# 104-de-8.net
KiCad netlist of a schematic drawn in EAGLE
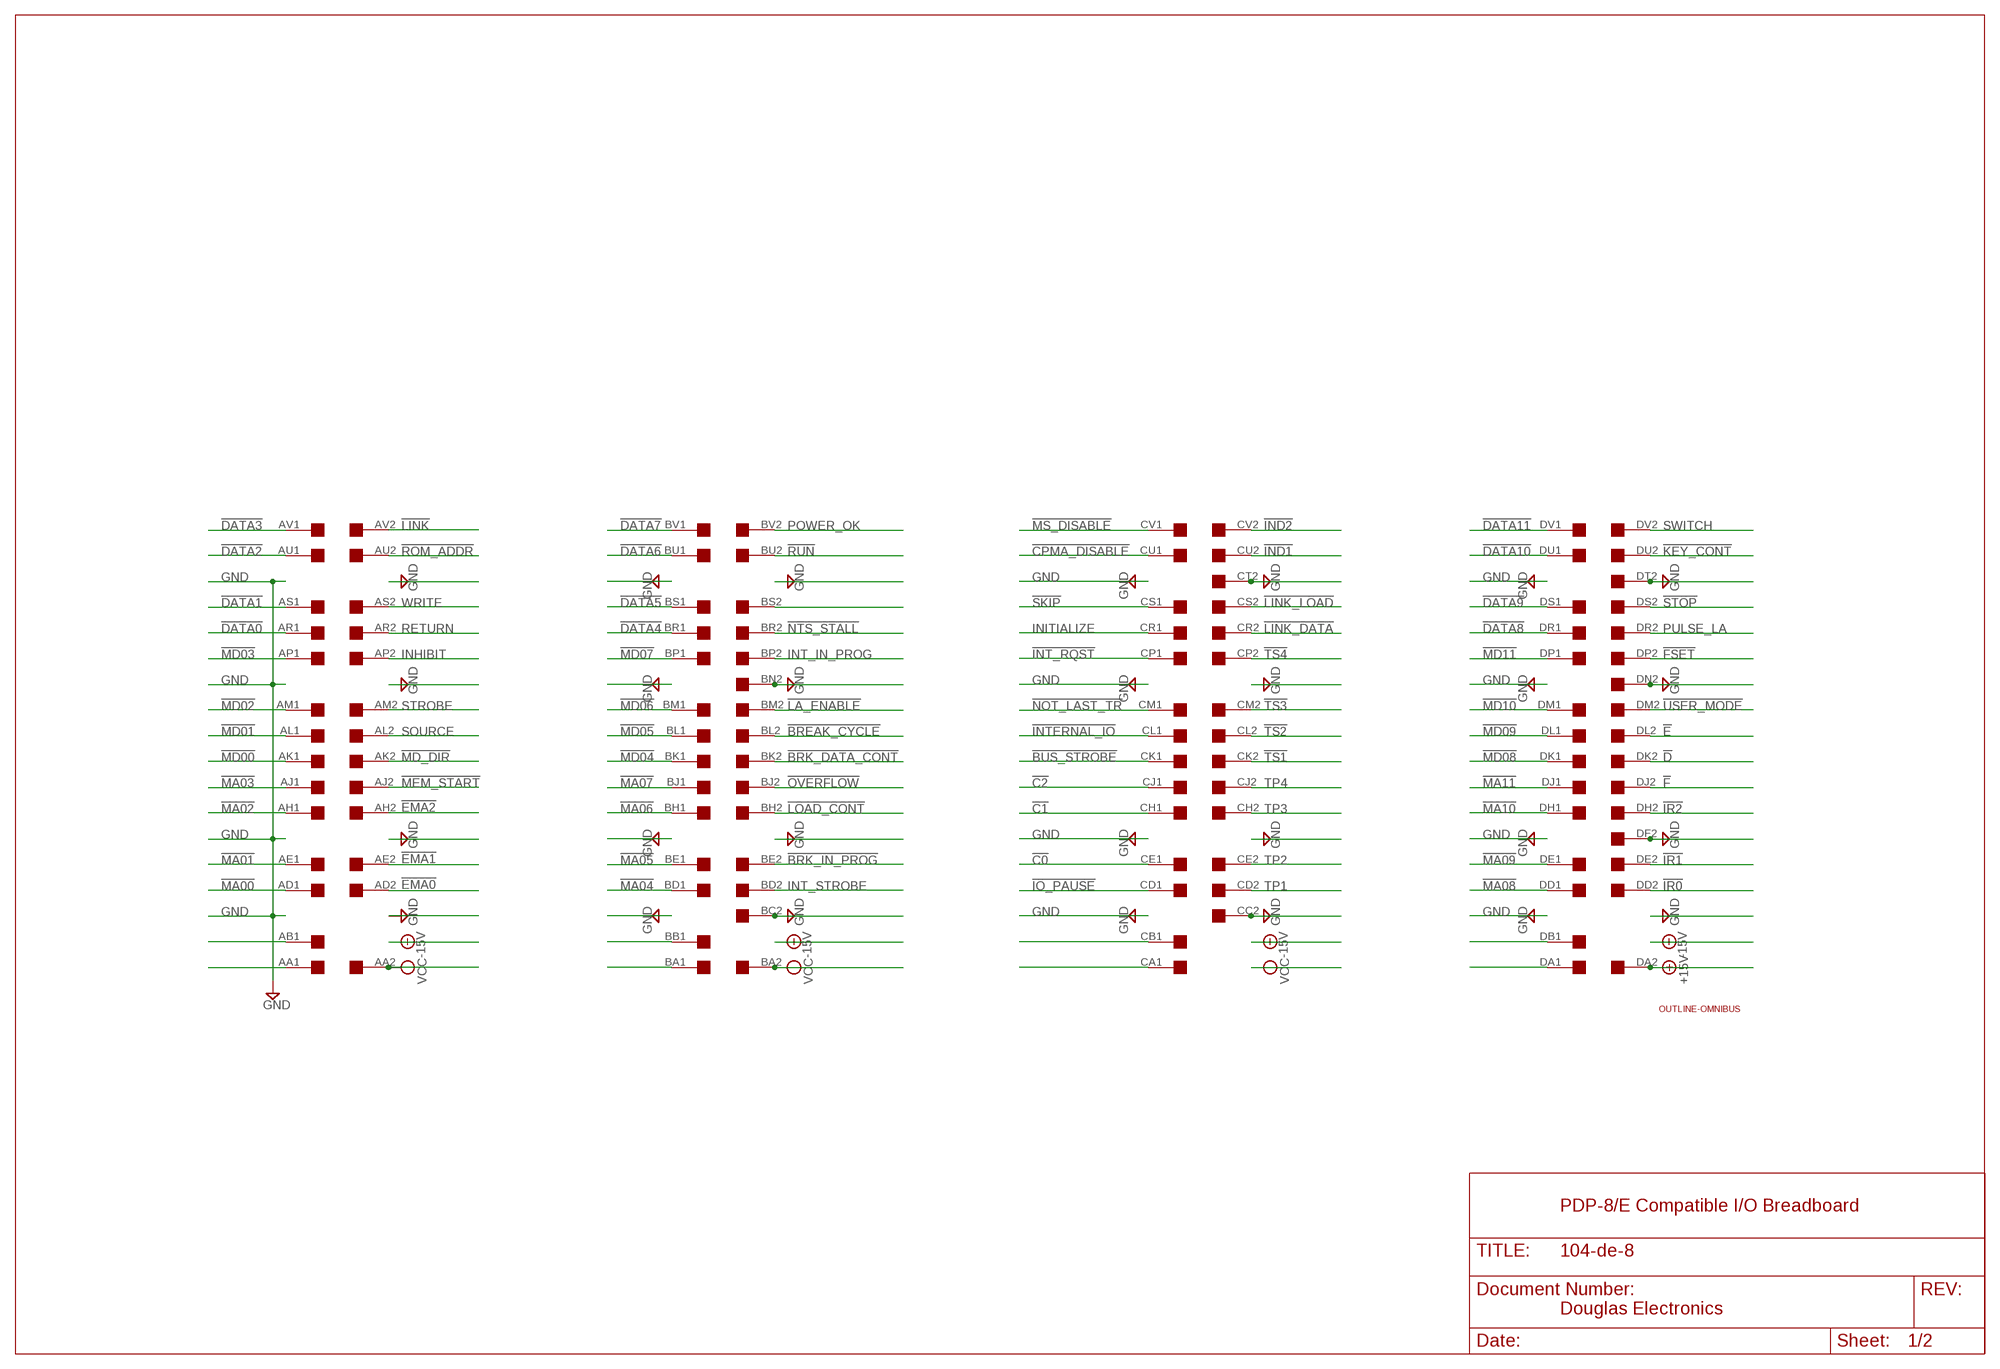
[diagram p0: schematic, sheet 1]
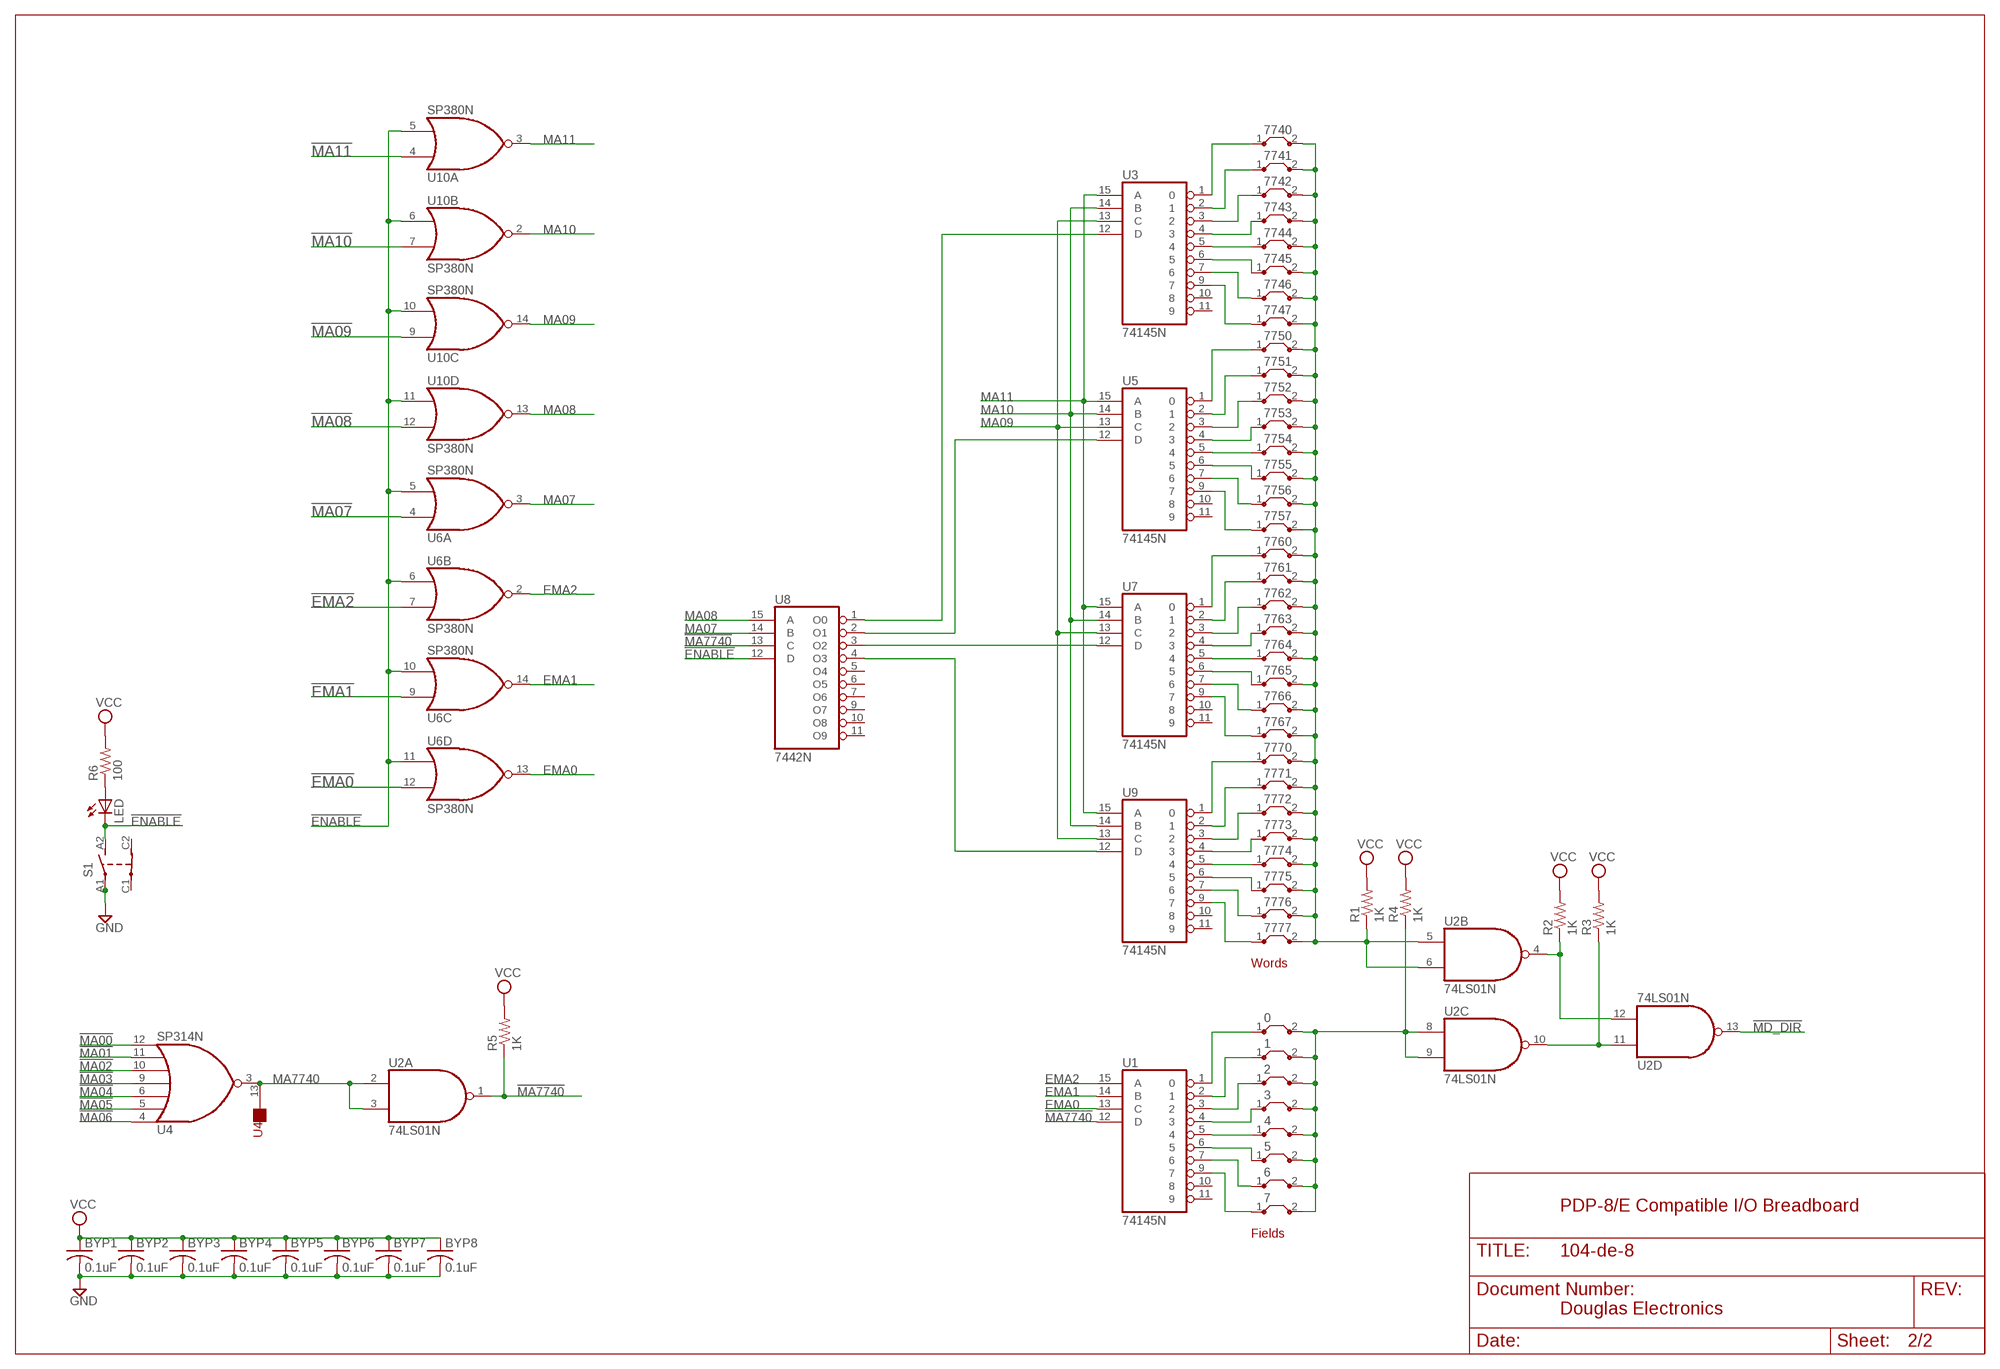
[diagram p1: schematic, sheet 2]

(export (version "E")
  (design (tool "Eeschema 10.0.6"))
  (components
    (comp (ref "0")
      (value "J5MM")
      (footprint "eagle-import:05")
      (libsource (lib "eagle-import") (part "J5MM"))
    )
    (comp (ref "1")
      (value "J5MM")
      (footprint "eagle-import:05")
      (libsource (lib "eagle-import") (part "J5MM"))
    )
    (comp (ref "2")
      (value "J5MM")
      (footprint "eagle-import:05")
      (libsource (lib "eagle-import") (part "J5MM"))
    )
    (comp (ref "3")
      (value "J5MM")
      (footprint "eagle-import:05")
      (libsource (lib "eagle-import") (part "J5MM"))
    )
    (comp (ref "4")
      (value "J5MM")
      (footprint "eagle-import:05")
      (libsource (lib "eagle-import") (part "J5MM"))
    )
    (comp (ref "5")
      (value "J5MM")
      (footprint "eagle-import:05")
      (libsource (lib "eagle-import") (part "J5MM"))
    )
    (comp (ref "6")
      (value "J5MM")
      (footprint "eagle-import:05")
      (libsource (lib "eagle-import") (part "J5MM"))
    )
    (comp (ref "7")
      (value "J5MM")
      (footprint "eagle-import:05")
      (libsource (lib "eagle-import") (part "J5MM"))
    )
    (comp (ref "7740")
      (value "J5MM")
      (footprint "eagle-import:05")
      (libsource (lib "eagle-import") (part "J5MM"))
    )
    (comp (ref "7741")
      (value "J5MM")
      (footprint "eagle-import:05")
      (libsource (lib "eagle-import") (part "J5MM"))
    )
    (comp (ref "7742")
      (value "J5MM")
      (footprint "eagle-import:05")
      (libsource (lib "eagle-import") (part "J5MM"))
    )
    (comp (ref "7743")
      (value "J5MM")
      (footprint "eagle-import:05")
      (libsource (lib "eagle-import") (part "J5MM"))
    )
    (comp (ref "7744")
      (value "J5MM")
      (footprint "eagle-import:05")
      (libsource (lib "eagle-import") (part "J5MM"))
    )
    (comp (ref "7745")
      (value "J5MM")
      (footprint "eagle-import:05")
      (libsource (lib "eagle-import") (part "J5MM"))
    )
    (comp (ref "7746")
      (value "J5MM")
      (footprint "eagle-import:05")
      (libsource (lib "eagle-import") (part "J5MM"))
    )
    (comp (ref "7747")
      (value "J5MM")
      (footprint "eagle-import:05")
      (libsource (lib "eagle-import") (part "J5MM"))
    )
    (comp (ref "7750")
      (value "J5MM")
      (footprint "eagle-import:05")
      (libsource (lib "eagle-import") (part "J5MM"))
    )
    (comp (ref "7751")
      (value "J5MM")
      (footprint "eagle-import:05")
      (libsource (lib "eagle-import") (part "J5MM"))
    )
    (comp (ref "7752")
      (value "J5MM")
      (footprint "eagle-import:05")
      (libsource (lib "eagle-import") (part "J5MM"))
    )
    (comp (ref "7753")
      (value "J5MM")
      (footprint "eagle-import:05")
      (libsource (lib "eagle-import") (part "J5MM"))
    )
    (comp (ref "7754")
      (value "J5MM")
      (footprint "eagle-import:05")
      (libsource (lib "eagle-import") (part "J5MM"))
    )
    (comp (ref "7755")
      (value "J5MM")
      (footprint "eagle-import:05")
      (libsource (lib "eagle-import") (part "J5MM"))
    )
    (comp (ref "7756")
      (value "J5MM")
      (footprint "eagle-import:05")
      (libsource (lib "eagle-import") (part "J5MM"))
    )
    (comp (ref "7757")
      (value "J5MM")
      (footprint "eagle-import:05")
      (libsource (lib "eagle-import") (part "J5MM"))
    )
    (comp (ref "7760")
      (value "J5MM")
      (footprint "eagle-import:05")
      (libsource (lib "eagle-import") (part "J5MM"))
    )
    (comp (ref "7761")
      (value "J5MM")
      (footprint "eagle-import:05")
      (libsource (lib "eagle-import") (part "J5MM"))
    )
    (comp (ref "7762")
      (value "J5MM")
      (footprint "eagle-import:05")
      (libsource (lib "eagle-import") (part "J5MM"))
    )
    (comp (ref "7763")
      (value "J5MM")
      (footprint "eagle-import:05")
      (libsource (lib "eagle-import") (part "J5MM"))
    )
    (comp (ref "7764")
      (value "J5MM")
      (footprint "eagle-import:05")
      (libsource (lib "eagle-import") (part "J5MM"))
    )
    (comp (ref "7765")
      (value "J5MM")
      (footprint "eagle-import:05")
      (libsource (lib "eagle-import") (part "J5MM"))
    )
    (comp (ref "7766")
      (value "J5MM")
      (footprint "eagle-import:05")
      (libsource (lib "eagle-import") (part "J5MM"))
    )
    (comp (ref "7767")
      (value "J5MM")
      (footprint "eagle-import:05")
      (libsource (lib "eagle-import") (part "J5MM"))
    )
    (comp (ref "7770")
      (value "J5MM")
      (footprint "eagle-import:05")
      (libsource (lib "eagle-import") (part "J5MM"))
    )
    (comp (ref "7771")
      (value "J5MM")
      (footprint "eagle-import:05")
      (libsource (lib "eagle-import") (part "J5MM"))
    )
    (comp (ref "7772")
      (value "J5MM")
      (footprint "eagle-import:05")
      (libsource (lib "eagle-import") (part "J5MM"))
    )
    (comp (ref "7773")
      (value "J5MM")
      (footprint "eagle-import:05")
      (libsource (lib "eagle-import") (part "J5MM"))
    )
    (comp (ref "7774")
      (value "J5MM")
      (footprint "eagle-import:05")
      (libsource (lib "eagle-import") (part "J5MM"))
    )
    (comp (ref "7775")
      (value "J5MM")
      (footprint "eagle-import:05")
      (libsource (lib "eagle-import") (part "J5MM"))
    )
    (comp (ref "7776")
      (value "J5MM")
      (footprint "eagle-import:05")
      (libsource (lib "eagle-import") (part "J5MM"))
    )
    (comp (ref "7777")
      (value "J5MM")
      (footprint "eagle-import:05")
      (libsource (lib "eagle-import") (part "J5MM"))
    )
    (comp (ref "BYP1")
      (value "0.1uF")
      (footprint "eagle-import:C063-025X075")
      (libsource (lib "eagle-import") (part "C-US"))
    )
    (comp (ref "BYP2")
      (value "0.1uF")
      (footprint "eagle-import:C063-025X075")
      (libsource (lib "eagle-import") (part "C-US"))
    )
    (comp (ref "BYP3")
      (value "0.1uF")
      (footprint "eagle-import:C063-025X075")
      (libsource (lib "eagle-import") (part "C-US"))
    )
    (comp (ref "BYP4")
      (value "0.1uF")
      (footprint "eagle-import:C063-025X075")
      (libsource (lib "eagle-import") (part "C-US"))
    )
    (comp (ref "BYP5")
      (value "0.1uF")
      (footprint "eagle-import:C063-025X075")
      (libsource (lib "eagle-import") (part "C-US"))
    )
    (comp (ref "BYP6")
      (value "0.1uF")
      (footprint "eagle-import:C063-025X075")
      (libsource (lib "eagle-import") (part "C-US"))
    )
    (comp (ref "BYP7")
      (value "0.1uF")
      (footprint "eagle-import:C063-025X075")
      (libsource (lib "eagle-import") (part "C-US"))
    )
    (comp (ref "BYP8")
      (value "0.1uF")
      (footprint "eagle-import:C063-025X075")
      (libsource (lib "eagle-import") (part "C-US"))
    )
    (comp (ref "LED")
      (value "LED5MM")
      (footprint "eagle-import:LED5MM")
      (libsource (lib "eagle-import") (part "LED5MM"))
    )
    (comp (ref "R1")
      (value "1K")
      (footprint "eagle-import:0207_10")
      (libsource (lib "eagle-import") (part "R-US_0207/10"))
    )
    (comp (ref "R2")
      (value "1K")
      (footprint "eagle-import:0207_10")
      (libsource (lib "eagle-import") (part "R-US_0207/10"))
    )
    (comp (ref "R3")
      (value "1K")
      (footprint "eagle-import:0207_10")
      (libsource (lib "eagle-import") (part "R-US_0207/10"))
    )
    (comp (ref "R4")
      (value "1K")
      (footprint "eagle-import:0207_10")
      (libsource (lib "eagle-import") (part "R-US_0207/10"))
    )
    (comp (ref "R5")
      (value "1K")
      (footprint "eagle-import:0207_10")
      (libsource (lib "eagle-import") (part "R-US_0207/10"))
    )
    (comp (ref "R6")
      (value "100")
      (footprint "eagle-import:0207_10")
      (libsource (lib "eagle-import") (part "R-US_0207/10"))
    )
    (comp (ref "S1")
      (value "T8201")
      (footprint "eagle-import:T8000")
      (libsource (lib "eagle-import") (part "T8201"))
    )
    (comp (ref "U1")
      (value "74145N")
      (footprint "eagle-import:DIL16")
      (libsource (lib "eagle-import") (part "74145N"))
    )
    (comp (ref "U2")
      (value "74LS01N")
      (footprint "eagle-import:DIL14")
      (libsource (lib "eagle-import") (part "7401NLS"))
    )
    (comp (ref "U3")
      (value "74145N")
      (footprint "eagle-import:DIL16")
      (libsource (lib "eagle-import") (part "74145N"))
    )
    (comp (ref "U4")
      (value "SP314N")
      (footprint "eagle-import:DIL14")
      (libsource (lib "eagle-import") (part "SP314N"))
    )
    (comp (ref "U5")
      (value "74145N")
      (footprint "eagle-import:DIL16")
      (libsource (lib "eagle-import") (part "74145N"))
    )
    (comp (ref "U6")
      (value "SP380N")
      (footprint "eagle-import:DIL14")
      (libsource (lib "eagle-import") (part "SP380N"))
    )
    (comp (ref "U7")
      (value "74145N")
      (footprint "eagle-import:DIL16")
      (libsource (lib "eagle-import") (part "74145N"))
    )
    (comp (ref "U8")
      (value "7442N")
      (footprint "eagle-import:DIL16")
      (libsource (lib "eagle-import") (part "7442NLS"))
    )
    (comp (ref "U9")
      (value "74145N")
      (footprint "eagle-import:DIL16")
      (libsource (lib "eagle-import") (part "74145N"))
    )
    (comp (ref "U10")
      (value "SP380N")
      (footprint "eagle-import:DIL14")
      (libsource (lib "eagle-import") (part "SP380N"))
    )
    (comp (ref "U$1")
      (value "OUTLINE-OMNIBUS")
      (footprint "eagle-import:OMNIBUS")
      (libsource (lib "eagle-import") (part "OUTLINE-OMNIBUS"))
    )
    (comp (ref "U$2")
      (value "QUAD")
      (footprint "eagle-import:EDGE-CON8")
      (libsource (lib "eagle-import") (part "QUAD"))
    )
  )
  (nets
    (net (code "1") (name "+15V") (class "Default")
      (node (ref "U$2") (pin "DA2") (pinfunction "1_DA2") (pintype "bidirectional"))
    )
    (net (code "3") (name "EMA0") (class "Default")
      (node (ref "U1") (pin "13") (pinfunction "C_13") (pintype "input"))
      (node (ref "U6") (pin "13") (pinfunction "O_13") (pintype "output"))
    )
    (net (code "4") (name "EMA1") (class "Default")
      (node (ref "U1") (pin "14") (pinfunction "B_14") (pintype "input"))
      (node (ref "U6") (pin "14") (pinfunction "O_14") (pintype "output"))
    )
    (net (code "5") (name "EMA2") (class "Default")
      (node (ref "U1") (pin "15") (pinfunction "A_15") (pintype "input"))
      (node (ref "U6") (pin "2") (pinfunction "O_2") (pintype "output"))
    )
    (net (code "6") (name "GND") (class "Default")
      (node (ref "BYP1") (pin "2") (pinfunction "2_2") (pintype "passive"))
      (node (ref "BYP2") (pin "2") (pinfunction "2_2") (pintype "passive"))
      (node (ref "BYP3") (pin "2") (pinfunction "2_2") (pintype "passive"))
      (node (ref "BYP4") (pin "2") (pinfunction "2_2") (pintype "passive"))
      (node (ref "BYP5") (pin "2") (pinfunction "2_2") (pintype "passive"))
      (node (ref "BYP6") (pin "2") (pinfunction "2_2") (pintype "passive"))
      (node (ref "BYP7") (pin "2") (pinfunction "2_2") (pintype "passive"))
      (node (ref "BYP8") (pin "2") (pinfunction "2_2") (pintype "passive"))
      (node (ref "S1") (pin "A1") (pinfunction "A1_A1") (pintype "passive"))
      (node (ref "U$2") (pin "BC2") (pinfunction "1_BC2") (pintype "bidirectional"))
      (node (ref "U$2") (pin "BN2") (pinfunction "1_BN2") (pintype "bidirectional"))
      (node (ref "U$2") (pin "CC2") (pinfunction "1_CC2") (pintype "bidirectional"))
      (node (ref "U$2") (pin "CT2") (pinfunction "1_CT2") (pintype "bidirectional"))
      (node (ref "U$2") (pin "DF2") (pinfunction "1_DF2") (pintype "bidirectional"))
      (node (ref "U$2") (pin "DN2") (pinfunction "1_DN2") (pintype "bidirectional"))
      (node (ref "U$2") (pin "DT2") (pinfunction "1_DT2") (pintype "bidirectional"))
    )
    (net (code "7") (name "INHIBIT") (class "Default")
      (node (ref "U$2") (pin "AP2") (pinfunction "1_AP2") (pintype "bidirectional"))
    )
    (net (code "8") (name "INITIALIZE") (class "Default")
      (node (ref "U$2") (pin "CR1") (pinfunction "1_CR1") (pintype "bidirectional"))
    )
    (net (code "9") (name "INT_IN_PROG") (class "Default")
      (node (ref "U$2") (pin "BP2") (pinfunction "1_BP2") (pintype "bidirectional"))
    )
    (net (code "10") (name "INT_STROBE") (class "Default")
      (node (ref "U$2") (pin "BD2") (pinfunction "1_BD2") (pintype "bidirectional"))
    )
    (net (code "11") (name "MA07") (class "Default")
      (node (ref "U6") (pin "3") (pinfunction "O_3") (pintype "output"))
      (node (ref "U8") (pin "14") (pinfunction "B_14") (pintype "input"))
    )
    (net (code "12") (name "MA08") (class "Default")
      (node (ref "U10") (pin "13") (pinfunction "O_13") (pintype "output"))
      (node (ref "U8") (pin "15") (pinfunction "A_15") (pintype "input"))
    )
    (net (code "13") (name "MA09") (class "Default")
      (node (ref "U10") (pin "14") (pinfunction "O_14") (pintype "output"))
      (node (ref "U3") (pin "13") (pinfunction "C_13") (pintype "input"))
      (node (ref "U5") (pin "13") (pinfunction "C_13") (pintype "input"))
      (node (ref "U7") (pin "13") (pinfunction "C_13") (pintype "input"))
      (node (ref "U9") (pin "13") (pinfunction "C_13") (pintype "input"))
    )
    (net (code "14") (name "MA10") (class "Default")
      (node (ref "U10") (pin "2") (pinfunction "O_2") (pintype "output"))
      (node (ref "U3") (pin "14") (pinfunction "B_14") (pintype "input"))
      (node (ref "U5") (pin "14") (pinfunction "B_14") (pintype "input"))
      (node (ref "U7") (pin "14") (pinfunction "B_14") (pintype "input"))
      (node (ref "U9") (pin "14") (pinfunction "B_14") (pintype "input"))
    )
    (net (code "15") (name "MA11") (class "Default")
      (node (ref "U10") (pin "3") (pinfunction "O_3") (pintype "output"))
      (node (ref "U3") (pin "15") (pinfunction "A_15") (pintype "input"))
      (node (ref "U5") (pin "15") (pinfunction "A_15") (pintype "input"))
      (node (ref "U7") (pin "15") (pinfunction "A_15") (pintype "input"))
      (node (ref "U9") (pin "15") (pinfunction "A_15") (pintype "input"))
    )
    (net (code "16") (name "MA7740") (class "Default")
      (node (ref "U2") (pin "2") (pinfunction "I0_2") (pintype "input"))
      (node (ref "U2") (pin "3") (pinfunction "I1_3") (pintype "input"))
      (node (ref "U4") (pin "13") (pinfunction "NC_13") (pintype "passive"))
      (node (ref "U4") (pin "3") (pinfunction "O_3") (pintype "output"))
    )
    (net (code "17") (name "Net-(LED-PadA)") (class "Default")
      (node (ref "LED") (pin "A") (pinfunction "A_A") (pintype "passive"))
      (node (ref "R6") (pin "1") (pinfunction "1_1") (pintype "passive"))
    )
    (net (code "18") (name "Net-(U1A-0)") (class "Default")
      (node (ref "0") (pin "1") (pinfunction "1_1") (pintype "passive"))
      (node (ref "U1") (pin "1") (pinfunction "0_1") (pintype "output"))
    )
    (net (code "19") (name "Net-(U1A-1)") (class "Default")
      (node (ref "1") (pin "1") (pinfunction "1_1") (pintype "passive"))
      (node (ref "U1") (pin "2") (pinfunction "1_2") (pintype "output"))
    )
    (net (code "20") (name "Net-(U1A-2)") (class "Default")
      (node (ref "2") (pin "1") (pinfunction "1_1") (pintype "passive"))
      (node (ref "U1") (pin "3") (pinfunction "2_3") (pintype "output"))
    )
    (net (code "21") (name "Net-(U1A-3)") (class "Default")
      (node (ref "3") (pin "1") (pinfunction "1_1") (pintype "passive"))
      (node (ref "U1") (pin "4") (pinfunction "3_4") (pintype "output"))
    )
    (net (code "22") (name "Net-(U1A-4)") (class "Default")
      (node (ref "4") (pin "1") (pinfunction "1_1") (pintype "passive"))
      (node (ref "U1") (pin "5") (pinfunction "4_5") (pintype "output"))
    )
    (net (code "23") (name "Net-(U1A-5)") (class "Default")
      (node (ref "5") (pin "1") (pinfunction "1_1") (pintype "passive"))
      (node (ref "U1") (pin "6") (pinfunction "5_6") (pintype "output"))
    )
    (net (code "24") (name "Net-(U1A-6)") (class "Default")
      (node (ref "6") (pin "1") (pinfunction "1_1") (pintype "passive"))
      (node (ref "U1") (pin "7") (pinfunction "6_7") (pintype "output"))
    )
    (net (code "25") (name "Net-(U1A-7)") (class "Default")
      (node (ref "7") (pin "1") (pinfunction "1_1") (pintype "passive"))
      (node (ref "U1") (pin "9") (pinfunction "7_9") (pintype "output"))
    )
    (net (code "26") (name "Net-(U2B-I0)") (class "Default")
      (node (ref "7740") (pin "2") (pinfunction "2_2") (pintype "passive"))
      (node (ref "7741") (pin "2") (pinfunction "2_2") (pintype "passive"))
      (node (ref "7742") (pin "2") (pinfunction "2_2") (pintype "passive"))
      (node (ref "7743") (pin "2") (pinfunction "2_2") (pintype "passive"))
      (node (ref "7744") (pin "2") (pinfunction "2_2") (pintype "passive"))
      (node (ref "7745") (pin "2") (pinfunction "2_2") (pintype "passive"))
      (node (ref "7746") (pin "2") (pinfunction "2_2") (pintype "passive"))
      (node (ref "7747") (pin "2") (pinfunction "2_2") (pintype "passive"))
      (node (ref "7750") (pin "2") (pinfunction "2_2") (pintype "passive"))
      (node (ref "7751") (pin "2") (pinfunction "2_2") (pintype "passive"))
      (node (ref "7752") (pin "2") (pinfunction "2_2") (pintype "passive"))
      (node (ref "7753") (pin "2") (pinfunction "2_2") (pintype "passive"))
      (node (ref "7754") (pin "2") (pinfunction "2_2") (pintype "passive"))
      (node (ref "7755") (pin "2") (pinfunction "2_2") (pintype "passive"))
      (node (ref "7756") (pin "2") (pinfunction "2_2") (pintype "passive"))
      (node (ref "7757") (pin "2") (pinfunction "2_2") (pintype "passive"))
      (node (ref "7760") (pin "2") (pinfunction "2_2") (pintype "passive"))
      (node (ref "7761") (pin "2") (pinfunction "2_2") (pintype "passive"))
      (node (ref "7762") (pin "2") (pinfunction "2_2") (pintype "passive"))
      (node (ref "7763") (pin "2") (pinfunction "2_2") (pintype "passive"))
      (node (ref "7764") (pin "2") (pinfunction "2_2") (pintype "passive"))
      (node (ref "7765") (pin "2") (pinfunction "2_2") (pintype "passive"))
      (node (ref "7766") (pin "2") (pinfunction "2_2") (pintype "passive"))
      (node (ref "7767") (pin "2") (pinfunction "2_2") (pintype "passive"))
      (node (ref "7770") (pin "2") (pinfunction "2_2") (pintype "passive"))
      (node (ref "7771") (pin "2") (pinfunction "2_2") (pintype "passive"))
      (node (ref "7772") (pin "2") (pinfunction "2_2") (pintype "passive"))
      (node (ref "7773") (pin "2") (pinfunction "2_2") (pintype "passive"))
      (node (ref "7774") (pin "2") (pinfunction "2_2") (pintype "passive"))
      (node (ref "7775") (pin "2") (pinfunction "2_2") (pintype "passive"))
      (node (ref "7776") (pin "2") (pinfunction "2_2") (pintype "passive"))
      (node (ref "7777") (pin "2") (pinfunction "2_2") (pintype "passive"))
      (node (ref "R1") (pin "1") (pinfunction "1_1") (pintype "passive"))
      (node (ref "U2") (pin "5") (pinfunction "I0_5") (pintype "input"))
      (node (ref "U2") (pin "6") (pinfunction "I1_6") (pintype "input"))
    )
    (net (code "27") (name "Net-(U2B-O)") (class "Default")
      (node (ref "R2") (pin "1") (pinfunction "1_1") (pintype "passive"))
      (node (ref "U2") (pin "12") (pinfunction "I1_12") (pintype "input"))
      (node (ref "U2") (pin "4") (pinfunction "O_4") (pintype "open_collector"))
    )
    (net (code "28") (name "Net-(U2C-I0)") (class "Default")
      (node (ref "0") (pin "2") (pinfunction "2_2") (pintype "passive"))
      (node (ref "1") (pin "2") (pinfunction "2_2") (pintype "passive"))
      (node (ref "2") (pin "2") (pinfunction "2_2") (pintype "passive"))
      (node (ref "3") (pin "2") (pinfunction "2_2") (pintype "passive"))
      (node (ref "4") (pin "2") (pinfunction "2_2") (pintype "passive"))
      (node (ref "5") (pin "2") (pinfunction "2_2") (pintype "passive"))
      (node (ref "6") (pin "2") (pinfunction "2_2") (pintype "passive"))
      (node (ref "7") (pin "2") (pinfunction "2_2") (pintype "passive"))
      (node (ref "R4") (pin "1") (pinfunction "1_1") (pintype "passive"))
      (node (ref "U2") (pin "8") (pinfunction "I0_8") (pintype "input"))
      (node (ref "U2") (pin "9") (pinfunction "I1_9") (pintype "input"))
    )
    (net (code "29") (name "Net-(U2C-O)") (class "Default")
      (node (ref "R3") (pin "1") (pinfunction "1_1") (pintype "passive"))
      (node (ref "U2") (pin "10") (pinfunction "O_10") (pintype "open_collector"))
      (node (ref "U2") (pin "11") (pinfunction "I0_11") (pintype "input"))
    )
    (net (code "30") (name "Net-(U3A-0)") (class "Default")
      (node (ref "7740") (pin "1") (pinfunction "1_1") (pintype "passive"))
      (node (ref "U3") (pin "1") (pinfunction "0_1") (pintype "output"))
    )
    (net (code "31") (name "Net-(U3A-1)") (class "Default")
      (node (ref "7741") (pin "1") (pinfunction "1_1") (pintype "passive"))
      (node (ref "U3") (pin "2") (pinfunction "1_2") (pintype "output"))
    )
    (net (code "32") (name "Net-(U3A-2)") (class "Default")
      (node (ref "7742") (pin "1") (pinfunction "1_1") (pintype "passive"))
      (node (ref "U3") (pin "3") (pinfunction "2_3") (pintype "output"))
    )
    (net (code "33") (name "Net-(U3A-3)") (class "Default")
      (node (ref "7743") (pin "1") (pinfunction "1_1") (pintype "passive"))
      (node (ref "U3") (pin "4") (pinfunction "3_4") (pintype "output"))
    )
    (net (code "34") (name "Net-(U3A-4)") (class "Default")
      (node (ref "7744") (pin "1") (pinfunction "1_1") (pintype "passive"))
      (node (ref "U3") (pin "5") (pinfunction "4_5") (pintype "output"))
    )
    (net (code "35") (name "Net-(U3A-5)") (class "Default")
      (node (ref "7745") (pin "1") (pinfunction "1_1") (pintype "passive"))
      (node (ref "U3") (pin "6") (pinfunction "5_6") (pintype "output"))
    )
    (net (code "36") (name "Net-(U3A-6)") (class "Default")
      (node (ref "7746") (pin "1") (pinfunction "1_1") (pintype "passive"))
      (node (ref "U3") (pin "7") (pinfunction "6_7") (pintype "output"))
    )
    (net (code "37") (name "Net-(U3A-7)") (class "Default")
      (node (ref "7747") (pin "1") (pinfunction "1_1") (pintype "passive"))
      (node (ref "U3") (pin "9") (pinfunction "7_9") (pintype "output"))
    )
    (net (code "38") (name "Net-(U3A-D)") (class "Default")
      (node (ref "U3") (pin "12") (pinfunction "D_12") (pintype "input"))
      (node (ref "U8") (pin "1") (pinfunction "O0_1") (pintype "output"))
    )
    (net (code "39") (name "Net-(U5A-0)") (class "Default")
      (node (ref "7750") (pin "1") (pinfunction "1_1") (pintype "passive"))
      (node (ref "U5") (pin "1") (pinfunction "0_1") (pintype "output"))
    )
    (net (code "40") (name "Net-(U5A-1)") (class "Default")
      (node (ref "7751") (pin "1") (pinfunction "1_1") (pintype "passive"))
      (node (ref "U5") (pin "2") (pinfunction "1_2") (pintype "output"))
    )
    (net (code "41") (name "Net-(U5A-2)") (class "Default")
      (node (ref "7752") (pin "1") (pinfunction "1_1") (pintype "passive"))
      (node (ref "U5") (pin "3") (pinfunction "2_3") (pintype "output"))
    )
    (net (code "42") (name "Net-(U5A-3)") (class "Default")
      (node (ref "7753") (pin "1") (pinfunction "1_1") (pintype "passive"))
      (node (ref "U5") (pin "4") (pinfunction "3_4") (pintype "output"))
    )
    (net (code "43") (name "Net-(U5A-4)") (class "Default")
      (node (ref "7754") (pin "1") (pinfunction "1_1") (pintype "passive"))
      (node (ref "U5") (pin "5") (pinfunction "4_5") (pintype "output"))
    )
    (net (code "44") (name "Net-(U5A-5)") (class "Default")
      (node (ref "7755") (pin "1") (pinfunction "1_1") (pintype "passive"))
      (node (ref "U5") (pin "6") (pinfunction "5_6") (pintype "output"))
    )
    (net (code "45") (name "Net-(U5A-6)") (class "Default")
      (node (ref "7756") (pin "1") (pinfunction "1_1") (pintype "passive"))
      (node (ref "U5") (pin "7") (pinfunction "6_7") (pintype "output"))
    )
    (net (code "46") (name "Net-(U5A-7)") (class "Default")
      (node (ref "7757") (pin "1") (pinfunction "1_1") (pintype "passive"))
      (node (ref "U5") (pin "9") (pinfunction "7_9") (pintype "output"))
    )
    (net (code "47") (name "Net-(U5A-D)") (class "Default")
      (node (ref "U5") (pin "12") (pinfunction "D_12") (pintype "input"))
      (node (ref "U8") (pin "2") (pinfunction "O1_2") (pintype "output"))
    )
    (net (code "48") (name "Net-(U7A-0)") (class "Default")
      (node (ref "7760") (pin "1") (pinfunction "1_1") (pintype "passive"))
      (node (ref "U7") (pin "1") (pinfunction "0_1") (pintype "output"))
    )
    (net (code "49") (name "Net-(U7A-1)") (class "Default")
      (node (ref "7761") (pin "1") (pinfunction "1_1") (pintype "passive"))
      (node (ref "U7") (pin "2") (pinfunction "1_2") (pintype "output"))
    )
    (net (code "50") (name "Net-(U7A-2)") (class "Default")
      (node (ref "7762") (pin "1") (pinfunction "1_1") (pintype "passive"))
      (node (ref "U7") (pin "3") (pinfunction "2_3") (pintype "output"))
    )
    (net (code "51") (name "Net-(U7A-3)") (class "Default")
      (node (ref "7763") (pin "1") (pinfunction "1_1") (pintype "passive"))
      (node (ref "U7") (pin "4") (pinfunction "3_4") (pintype "output"))
    )
    (net (code "52") (name "Net-(U7A-4)") (class "Default")
      (node (ref "7764") (pin "1") (pinfunction "1_1") (pintype "passive"))
      (node (ref "U7") (pin "5") (pinfunction "4_5") (pintype "output"))
    )
    (net (code "53") (name "Net-(U7A-5)") (class "Default")
      (node (ref "7765") (pin "1") (pinfunction "1_1") (pintype "passive"))
      (node (ref "U7") (pin "6") (pinfunction "5_6") (pintype "output"))
    )
    (net (code "54") (name "Net-(U7A-6)") (class "Default")
      (node (ref "7766") (pin "1") (pinfunction "1_1") (pintype "passive"))
      (node (ref "U7") (pin "7") (pinfunction "6_7") (pintype "output"))
    )
    (net (code "55") (name "Net-(U7A-7)") (class "Default")
      (node (ref "7767") (pin "1") (pinfunction "1_1") (pintype "passive"))
      (node (ref "U7") (pin "9") (pinfunction "7_9") (pintype "output"))
    )
    (net (code "56") (name "Net-(U7A-D)") (class "Default")
      (node (ref "U7") (pin "12") (pinfunction "D_12") (pintype "input"))
      (node (ref "U8") (pin "3") (pinfunction "O2_3") (pintype "output"))
    )
    (net (code "57") (name "Net-(U8A-O3)") (class "Default")
      (node (ref "U8") (pin "4") (pinfunction "O3_4") (pintype "output"))
      (node (ref "U9") (pin "12") (pinfunction "D_12") (pintype "input"))
    )
    (net (code "58") (name "Net-(U9A-0)") (class "Default")
      (node (ref "7770") (pin "1") (pinfunction "1_1") (pintype "passive"))
      (node (ref "U9") (pin "1") (pinfunction "0_1") (pintype "output"))
    )
    (net (code "59") (name "Net-(U9A-1)") (class "Default")
      (node (ref "7771") (pin "1") (pinfunction "1_1") (pintype "passive"))
      (node (ref "U9") (pin "2") (pinfunction "1_2") (pintype "output"))
    )
    (net (code "60") (name "Net-(U9A-2)") (class "Default")
      (node (ref "7772") (pin "1") (pinfunction "1_1") (pintype "passive"))
      (node (ref "U9") (pin "3") (pinfunction "2_3") (pintype "output"))
    )
    (net (code "61") (name "Net-(U9A-3)") (class "Default")
      (node (ref "7773") (pin "1") (pinfunction "1_1") (pintype "passive"))
      (node (ref "U9") (pin "4") (pinfunction "3_4") (pintype "output"))
    )
    (net (code "62") (name "Net-(U9A-4)") (class "Default")
      (node (ref "7774") (pin "1") (pinfunction "1_1") (pintype "passive"))
      (node (ref "U9") (pin "5") (pinfunction "4_5") (pintype "output"))
    )
    (net (code "63") (name "Net-(U9A-5)") (class "Default")
      (node (ref "7775") (pin "1") (pinfunction "1_1") (pintype "passive"))
      (node (ref "U9") (pin "6") (pinfunction "5_6") (pintype "output"))
    )
    (net (code "64") (name "Net-(U9A-6)") (class "Default")
      (node (ref "7776") (pin "1") (pinfunction "1_1") (pintype "passive"))
      (node (ref "U9") (pin "7") (pinfunction "6_7") (pintype "output"))
    )
    (net (code "65") (name "Net-(U9A-7)") (class "Default")
      (node (ref "7777") (pin "1") (pinfunction "1_1") (pintype "passive"))
      (node (ref "U9") (pin "9") (pinfunction "7_9") (pintype "output"))
    )
    (net (code "66") (name "POWER_OK") (class "Default")
      (node (ref "U$2") (pin "BV2") (pinfunction "1_BV2") (pintype "bidirectional"))
    )
    (net (code "67") (name "PULSE_LA") (class "Default")
      (node (ref "U$2") (pin "DR2") (pinfunction "1_DR2") (pintype "bidirectional"))
    )
    (net (code "68") (name "RETURN") (class "Default")
      (node (ref "U$2") (pin "AR2") (pinfunction "1_AR2") (pintype "bidirectional"))
    )
    (net (code "69") (name "SOURCE") (class "Default")
      (node (ref "U$2") (pin "AL2") (pinfunction "1_AL2") (pintype "bidirectional"))
    )
    (net (code "70") (name "STROBE") (class "Default")
      (node (ref "U$2") (pin "AM2") (pinfunction "1_AM2") (pintype "bidirectional"))
    )
    (net (code "71") (name "SWITCH") (class "Default")
      (node (ref "U$2") (pin "DV2") (pinfunction "1_DV2") (pintype "bidirectional"))
    )
    (net (code "72") (name "TP1") (class "Default")
      (node (ref "U$2") (pin "CD2") (pinfunction "1_CD2") (pintype "bidirectional"))
    )
    (net (code "73") (name "TP2") (class "Default")
      (node (ref "U$2") (pin "CE2") (pinfunction "1_CE2") (pintype "bidirectional"))
    )
    (net (code "74") (name "TP3") (class "Default")
      (node (ref "U$2") (pin "CH2") (pinfunction "1_CH2") (pintype "bidirectional"))
    )
    (net (code "75") (name "TP4") (class "Default")
      (node (ref "U$2") (pin "CJ2") (pinfunction "1_CJ2") (pintype "bidirectional"))
    )
    (net (code "76") (name "VCC") (class "Default")
      (node (ref "BYP1") (pin "1") (pinfunction "1_1") (pintype "passive"))
      (node (ref "BYP2") (pin "1") (pinfunction "1_1") (pintype "passive"))
      (node (ref "BYP3") (pin "1") (pinfunction "1_1") (pintype "passive"))
      (node (ref "BYP4") (pin "1") (pinfunction "1_1") (pintype "passive"))
      (node (ref "BYP5") (pin "1") (pinfunction "1_1") (pintype "passive"))
      (node (ref "BYP6") (pin "1") (pinfunction "1_1") (pintype "passive"))
      (node (ref "BYP7") (pin "1") (pinfunction "1_1") (pintype "passive"))
      (node (ref "BYP8") (pin "1") (pinfunction "1_1") (pintype "passive"))
      (node (ref "R1") (pin "2") (pinfunction "2_2") (pintype "passive"))
      (node (ref "R2") (pin "2") (pinfunction "2_2") (pintype "passive"))
      (node (ref "R3") (pin "2") (pinfunction "2_2") (pintype "passive"))
      (node (ref "R4") (pin "2") (pinfunction "2_2") (pintype "passive"))
      (node (ref "R5") (pin "2") (pinfunction "2_2") (pintype "passive"))
      (node (ref "R6") (pin "2") (pinfunction "2_2") (pintype "passive"))
      (node (ref "U$2") (pin "AA2") (pinfunction "1_AA2") (pintype "bidirectional"))
      (node (ref "U$2") (pin "BA2") (pinfunction "1_BA2") (pintype "bidirectional"))
    )
    (net (code "77") (name "WRITE") (class "Default")
      (node (ref "U$2") (pin "AS2") (pinfunction "1_AS2") (pintype "bidirectional"))
    )
    (net (code "78") (name "unconnected-(S1-PadC1)") (class "Default")
      (node (ref "S1") (pin "C1") (pinfunction "C1_C1") (pintype "passive"))
    )
    (net (code "79") (name "unconnected-(S1-PadC2)") (class "Default")
      (node (ref "S1") (pin "C2") (pinfunction "C2_C2") (pintype "passive"))
    )
    (net (code "80") (name "unconnected-(U$2A-1-PadAA1)") (class "Default")
      (node (ref "U$2") (pin "AA1") (pinfunction "1_AA1") (pintype "bidirectional"))
    )
    (net (code "81") (name "unconnected-(U$2AK-1-PadBA1)") (class "Default")
      (node (ref "U$2") (pin "BA1") (pinfunction "1_BA1") (pintype "bidirectional"))
    )
    (net (code "82") (name "unconnected-(U$2AM-1-PadBB1)") (class "Default")
      (node (ref "U$2") (pin "BB1") (pinfunction "1_BB1") (pintype "bidirectional"))
    )
    (net (code "83") (name "unconnected-(U$2BN-1-PadBS2)") (class "Default")
      (node (ref "U$2") (pin "BS2") (pinfunction "1_BS2") (pintype "bidirectional"))
    )
    (net (code "84") (name "unconnected-(U$2BU-1-PadCA1)") (class "Default")
      (node (ref "U$2") (pin "CA1") (pinfunction "1_CA1") (pintype "bidirectional"))
    )
    (net (code "85") (name "unconnected-(U$2BW-1-PadCB1)") (class "Default")
      (node (ref "U$2") (pin "CB1") (pinfunction "1_CB1") (pintype "bidirectional"))
    )
    (net (code "86") (name "unconnected-(U$2C-1-PadAB1)") (class "Default")
      (node (ref "U$2") (pin "AB1") (pinfunction "1_AB1") (pintype "bidirectional"))
    )
    (net (code "87") (name "unconnected-(U$2DE-1-PadDA1)") (class "Default")
      (node (ref "U$2") (pin "DA1") (pinfunction "1_DA1") (pintype "bidirectional"))
    )
    (net (code "88") (name "unconnected-(U$2DG-1-PadDB1)") (class "Default")
      (node (ref "U$2") (pin "DB1") (pinfunction "1_DB1") (pintype "bidirectional"))
    )
    (net (code "89") (name "unconnected-(U1A-8-Pad10)") (class "Default")
      (node (ref "U1") (pin "10") (pinfunction "8_10") (pintype "output"))
    )
    (net (code "90") (name "unconnected-(U1A-9-Pad11)") (class "Default")
      (node (ref "U1") (pin "11") (pinfunction "9_11") (pintype "output"))
    )
    (net (code "91") (name "unconnected-(U3A-8-Pad10)") (class "Default")
      (node (ref "U3") (pin "10") (pinfunction "8_10") (pintype "output"))
    )
    (net (code "92") (name "unconnected-(U3A-9-Pad11)") (class "Default")
      (node (ref "U3") (pin "11") (pinfunction "9_11") (pintype "output"))
    )
    (net (code "93") (name "unconnected-(U5A-8-Pad10)") (class "Default")
      (node (ref "U5") (pin "10") (pinfunction "8_10") (pintype "output"))
    )
    (net (code "94") (name "unconnected-(U5A-9-Pad11)") (class "Default")
      (node (ref "U5") (pin "11") (pinfunction "9_11") (pintype "output"))
    )
    (net (code "95") (name "unconnected-(U7A-8-Pad10)") (class "Default")
      (node (ref "U7") (pin "10") (pinfunction "8_10") (pintype "output"))
    )
    (net (code "96") (name "unconnected-(U7A-9-Pad11)") (class "Default")
      (node (ref "U7") (pin "11") (pinfunction "9_11") (pintype "output"))
    )
    (net (code "97") (name "unconnected-(U8A-O4-Pad5)") (class "Default")
      (node (ref "U8") (pin "5") (pinfunction "O4_5") (pintype "output"))
    )
    (net (code "98") (name "unconnected-(U8A-O5-Pad6)") (class "Default")
      (node (ref "U8") (pin "6") (pinfunction "O5_6") (pintype "output"))
    )
    (net (code "99") (name "unconnected-(U8A-O6-Pad7)") (class "Default")
      (node (ref "U8") (pin "7") (pinfunction "O6_7") (pintype "output"))
    )
    (net (code "100") (name "unconnected-(U8A-O7-Pad9)") (class "Default")
      (node (ref "U8") (pin "9") (pinfunction "O7_9") (pintype "output"))
    )
    (net (code "101") (name "unconnected-(U8A-O8-Pad10)") (class "Default")
      (node (ref "U8") (pin "10") (pinfunction "O8_10") (pintype "output"))
    )
    (net (code "102") (name "unconnected-(U8A-O9-Pad11)") (class "Default")
      (node (ref "U8") (pin "11") (pinfunction "O9_11") (pintype "output"))
    )
    (net (code "103") (name "unconnected-(U9A-8-Pad10)") (class "Default")
      (node (ref "U9") (pin "10") (pinfunction "8_10") (pintype "output"))
    )
    (net (code "104") (name "unconnected-(U9A-9-Pad11)") (class "Default")
      (node (ref "U9") (pin "11") (pinfunction "9_11") (pintype "output"))
    )
    (net (code "105") (name "~{BREAK_CYCLE}") (class "Default")
      (node (ref "U$2") (pin "BL2") (pinfunction "1_BL2") (pintype "bidirectional"))
    )
    (net (code "106") (name "~{BRK_DATA_CONT}") (class "Default")
      (node (ref "U$2") (pin "BK2") (pinfunction "1_BK2") (pintype "bidirectional"))
    )
    (net (code "107") (name "~{BRK_IN_PROG}") (class "Default")
      (node (ref "U$2") (pin "BE2") (pinfunction "1_BE2") (pintype "bidirectional"))
    )
    (net (code "108") (name "~{BUS_STROBE}") (class "Default")
      (node (ref "U$2") (pin "CK1") (pinfunction "1_CK1") (pintype "bidirectional"))
    )
    (net (code "109") (name "~{C0}") (class "Default")
      (node (ref "U$2") (pin "CE1") (pinfunction "1_CE1") (pintype "bidirectional"))
    )
    (net (code "110") (name "~{C1}") (class "Default")
      (node (ref "U$2") (pin "CH1") (pinfunction "1_CH1") (pintype "bidirectional"))
    )
    (net (code "111") (name "~{C2}") (class "Default")
      (node (ref "U$2") (pin "CJ1") (pinfunction "1_CJ1") (pintype "bidirectional"))
    )
    (net (code "112") (name "~{CPMA_DISABLE}") (class "Default")
      (node (ref "U$2") (pin "CU1") (pinfunction "1_CU1") (pintype "bidirectional"))
    )
    (net (code "113") (name "~{DATA0}") (class "Default")
      (node (ref "U$2") (pin "AR1") (pinfunction "1_AR1") (pintype "bidirectional"))
    )
    (net (code "114") (name "~{DATA1}") (class "Default")
      (node (ref "U$2") (pin "AS1") (pinfunction "1_AS1") (pintype "bidirectional"))
    )
    (net (code "115") (name "~{DATA2}") (class "Default")
      (node (ref "U$2") (pin "AU1") (pinfunction "1_AU1") (pintype "bidirectional"))
    )
    (net (code "116") (name "~{DATA3}") (class "Default")
      (node (ref "U$2") (pin "AV1") (pinfunction "1_AV1") (pintype "bidirectional"))
    )
    (net (code "117") (name "~{DATA4}") (class "Default")
      (node (ref "U$2") (pin "BR1") (pinfunction "1_BR1") (pintype "bidirectional"))
    )
    (net (code "118") (name "~{DATA5}") (class "Default")
      (node (ref "U$2") (pin "BS1") (pinfunction "1_BS1") (pintype "bidirectional"))
    )
    (net (code "119") (name "~{DATA6}") (class "Default")
      (node (ref "U$2") (pin "BU1") (pinfunction "1_BU1") (pintype "bidirectional"))
    )
    (net (code "120") (name "~{DATA7}") (class "Default")
      (node (ref "U$2") (pin "BV1") (pinfunction "1_BV1") (pintype "bidirectional"))
    )
    (net (code "121") (name "~{DATA8}") (class "Default")
      (node (ref "U$2") (pin "DR1") (pinfunction "1_DR1") (pintype "bidirectional"))
    )
    (net (code "122") (name "~{DATA9}") (class "Default")
      (node (ref "U$2") (pin "DS1") (pinfunction "1_DS1") (pintype "bidirectional"))
    )
    (net (code "123") (name "~{DATA10}") (class "Default")
      (node (ref "U$2") (pin "DU1") (pinfunction "1_DU1") (pintype "bidirectional"))
    )
    (net (code "124") (name "~{DATA11}") (class "Default")
      (node (ref "U$2") (pin "DV1") (pinfunction "1_DV1") (pintype "bidirectional"))
    )
    (net (code "125") (name "~{D}") (class "Default")
      (node (ref "U$2") (pin "DK2") (pinfunction "1_DK2") (pintype "bidirectional"))
    )
    (net (code "126") (name "~{EMA0}") (class "Default")
      (node (ref "U$2") (pin "AD2") (pinfunction "1_AD2") (pintype "bidirectional"))
      (node (ref "U6") (pin "12") (pinfunction "I1_12") (pintype "input"))
    )
    (net (code "127") (name "~{EMA1}") (class "Default")
      (node (ref "U$2") (pin "AE2") (pinfunction "1_AE2") (pintype "bidirectional"))
      (node (ref "U6") (pin "9") (pinfunction "I0_9") (pintype "input"))
    )
    (net (code "128") (name "~{EMA2}") (class "Default")
      (node (ref "U$2") (pin "AH2") (pinfunction "1_AH2") (pintype "bidirectional"))
      (node (ref "U6") (pin "7") (pinfunction "I1_7") (pintype "input"))
    )
    (net (code "129") (name "~{ENABLE}") (class "Default")
      (node (ref "LED") (pin "K") (pinfunction "C_K") (pintype "passive"))
      (node (ref "S1") (pin "A2") (pinfunction "A2_A2") (pintype "passive"))
      (node (ref "U10") (pin "10") (pinfunction "I1_10") (pintype "input"))
      (node (ref "U10") (pin "11") (pinfunction "I0_11") (pintype "input"))
      (node (ref "U10") (pin "5") (pinfunction "I1_5") (pintype "input"))
      (node (ref "U10") (pin "6") (pinfunction "I0_6") (pintype "input"))
      (node (ref "U6") (pin "10") (pinfunction "I1_10") (pintype "input"))
      (node (ref "U6") (pin "11") (pinfunction "I0_11") (pintype "input"))
      (node (ref "U6") (pin "5") (pinfunction "I1_5") (pintype "input"))
      (node (ref "U6") (pin "6") (pinfunction "I0_6") (pintype "input"))
      (node (ref "U8") (pin "12") (pinfunction "D_12") (pintype "input"))
    )
    (net (code "130") (name "~{E}") (class "Default")
      (node (ref "U$2") (pin "DL2") (pinfunction "1_DL2") (pintype "bidirectional"))
    )
    (net (code "131") (name "~{FSET}") (class "Default")
      (node (ref "U$2") (pin "DP2") (pinfunction "1_DP2") (pintype "bidirectional"))
    )
    (net (code "132") (name "~{F}") (class "Default")
      (node (ref "U$2") (pin "DJ2") (pinfunction "1_DJ2") (pintype "bidirectional"))
    )
    (net (code "133") (name "~{IND1}") (class "Default")
      (node (ref "U$2") (pin "CU2") (pinfunction "1_CU2") (pintype "bidirectional"))
    )
    (net (code "134") (name "~{IND2}") (class "Default")
      (node (ref "U$2") (pin "CV2") (pinfunction "1_CV2") (pintype "bidirectional"))
    )
    (net (code "135") (name "~{INTERNAL_IO}") (class "Default")
      (node (ref "U$2") (pin "CL1") (pinfunction "1_CL1") (pintype "bidirectional"))
    )
    (net (code "136") (name "~{INT_RQST}") (class "Default")
      (node (ref "U$2") (pin "CP1") (pinfunction "1_CP1") (pintype "bidirectional"))
    )
    (net (code "137") (name "~{IO_PAUSE}") (class "Default")
      (node (ref "U$2") (pin "CD1") (pinfunction "1_CD1") (pintype "bidirectional"))
    )
    (net (code "138") (name "~{IR0}") (class "Default")
      (node (ref "U$2") (pin "DD2") (pinfunction "1_DD2") (pintype "bidirectional"))
    )
    (net (code "139") (name "~{IR1}") (class "Default")
      (node (ref "U$2") (pin "DE2") (pinfunction "1_DE2") (pintype "bidirectional"))
    )
    (net (code "140") (name "~{IR2}") (class "Default")
      (node (ref "U$2") (pin "DH2") (pinfunction "1_DH2") (pintype "bidirectional"))
    )
    (net (code "141") (name "~{KEY_CONT}") (class "Default")
      (node (ref "U$2") (pin "DU2") (pinfunction "1_DU2") (pintype "bidirectional"))
    )
    (net (code "142") (name "~{LA_ENABLE}") (class "Default")
      (node (ref "U$2") (pin "BM2") (pinfunction "1_BM2") (pintype "bidirectional"))
    )
    (net (code "143") (name "~{LINK_DATA}") (class "Default")
      (node (ref "U$2") (pin "CR2") (pinfunction "1_CR2") (pintype "bidirectional"))
    )
    (net (code "144") (name "~{LINK_LOAD}") (class "Default")
      (node (ref "U$2") (pin "CS2") (pinfunction "1_CS2") (pintype "bidirectional"))
    )
    (net (code "145") (name "~{LINK}") (class "Default")
      (node (ref "U$2") (pin "AV2") (pinfunction "1_AV2") (pintype "bidirectional"))
    )
    (net (code "146") (name "~{LOAD_CONT}") (class "Default")
      (node (ref "U$2") (pin "BH2") (pinfunction "1_BH2") (pintype "bidirectional"))
    )
    (net (code "147") (name "~{MA00}") (class "Default")
      (node (ref "U$2") (pin "AD1") (pinfunction "1_AD1") (pintype "bidirectional"))
      (node (ref "U4") (pin "12") (pinfunction "I6_12") (pintype "input"))
    )
    (net (code "148") (name "~{MA01}") (class "Default")
      (node (ref "U$2") (pin "AE1") (pinfunction "1_AE1") (pintype "bidirectional"))
      (node (ref "U4") (pin "11") (pinfunction "I5_11") (pintype "input"))
    )
    (net (code "149") (name "~{MA02}") (class "Default")
      (node (ref "U$2") (pin "AH1") (pinfunction "1_AH1") (pintype "bidirectional"))
      (node (ref "U4") (pin "10") (pinfunction "I4_10") (pintype "input"))
    )
    (net (code "150") (name "~{MA03}") (class "Default")
      (node (ref "U$2") (pin "AJ1") (pinfunction "1_AJ1") (pintype "bidirectional"))
      (node (ref "U4") (pin "9") (pinfunction "I3_9") (pintype "input"))
    )
    (net (code "151") (name "~{MA04}") (class "Default")
      (node (ref "U$2") (pin "BD1") (pinfunction "1_BD1") (pintype "bidirectional"))
      (node (ref "U4") (pin "6") (pinfunction "I2_6") (pintype "input"))
    )
    (net (code "152") (name "~{MA05}") (class "Default")
      (node (ref "U$2") (pin "BE1") (pinfunction "1_BE1") (pintype "bidirectional"))
      (node (ref "U4") (pin "5") (pinfunction "I1_5") (pintype "input"))
    )
    (net (code "153") (name "~{MA06}") (class "Default")
      (node (ref "U$2") (pin "BH1") (pinfunction "1_BH1") (pintype "bidirectional"))
      (node (ref "U4") (pin "4") (pinfunction "I0_4") (pintype "input"))
    )
    (net (code "154") (name "~{MA07}") (class "Default")
      (node (ref "U$2") (pin "BJ1") (pinfunction "1_BJ1") (pintype "bidirectional"))
      (node (ref "U6") (pin "4") (pinfunction "I0_4") (pintype "input"))
    )
    (net (code "155") (name "~{MA08}") (class "Default")
      (node (ref "U$2") (pin "DD1") (pinfunction "1_DD1") (pintype "bidirectional"))
      (node (ref "U10") (pin "12") (pinfunction "I1_12") (pintype "input"))
    )
    (net (code "156") (name "~{MA09}") (class "Default")
      (node (ref "U$2") (pin "DE1") (pinfunction "1_DE1") (pintype "bidirectional"))
      (node (ref "U10") (pin "9") (pinfunction "I0_9") (pintype "input"))
    )
    (net (code "157") (name "~{MA10}") (class "Default")
      (node (ref "U$2") (pin "DH1") (pinfunction "1_DH1") (pintype "bidirectional"))
      (node (ref "U10") (pin "7") (pinfunction "I1_7") (pintype "input"))
    )
    (net (code "158") (name "~{MA11}") (class "Default")
      (node (ref "U$2") (pin "DJ1") (pinfunction "1_DJ1") (pintype "bidirectional"))
      (node (ref "U10") (pin "4") (pinfunction "I0_4") (pintype "input"))
    )
    (net (code "159") (name "~{MA7740}") (class "Default")
      (node (ref "R5") (pin "1") (pinfunction "1_1") (pintype "passive"))
      (node (ref "U1") (pin "12") (pinfunction "D_12") (pintype "input"))
      (node (ref "U2") (pin "1") (pinfunction "O_1") (pintype "open_collector"))
      (node (ref "U8") (pin "13") (pinfunction "C_13") (pintype "input"))
    )
    (net (code "160") (name "~{MD00}") (class "Default")
      (node (ref "U$2") (pin "AK1") (pinfunction "1_AK1") (pintype "bidirectional"))
    )
    (net (code "161") (name "~{MD01}") (class "Default")
      (node (ref "U$2") (pin "AL1") (pinfunction "1_AL1") (pintype "bidirectional"))
    )
    (net (code "162") (name "~{MD02}") (class "Default")
      (node (ref "U$2") (pin "AM1") (pinfunction "1_AM1") (pintype "bidirectional"))
    )
    (net (code "163") (name "~{MD03}") (class "Default")
      (node (ref "U$2") (pin "AP1") (pinfunction "1_AP1") (pintype "bidirectional"))
    )
    (net (code "164") (name "~{MD04}") (class "Default")
      (node (ref "U$2") (pin "BK1") (pinfunction "1_BK1") (pintype "bidirectional"))
    )
    (net (code "165") (name "~{MD05}") (class "Default")
      (node (ref "U$2") (pin "BL1") (pinfunction "1_BL1") (pintype "bidirectional"))
    )
    (net (code "166") (name "~{MD06}") (class "Default")
      (node (ref "U$2") (pin "BM1") (pinfunction "1_BM1") (pintype "bidirectional"))
    )
    (net (code "167") (name "~{MD07}") (class "Default")
      (node (ref "U$2") (pin "BP1") (pinfunction "1_BP1") (pintype "bidirectional"))
    )
    (net (code "168") (name "~{MD08}") (class "Default")
      (node (ref "U$2") (pin "DK1") (pinfunction "1_DK1") (pintype "bidirectional"))
    )
    (net (code "169") (name "~{MD09}") (class "Default")
      (node (ref "U$2") (pin "DL1") (pinfunction "1_DL1") (pintype "bidirectional"))
    )
    (net (code "170") (name "~{MD10}") (class "Default")
      (node (ref "U$2") (pin "DM1") (pinfunction "1_DM1") (pintype "bidirectional"))
    )
    (net (code "171") (name "~{MD11}") (class "Default")
      (node (ref "U$2") (pin "DP1") (pinfunction "1_DP1") (pintype "bidirectional"))
    )
    (net (code "172") (name "~{MD_DIR}") (class "Default")
      (node (ref "U$2") (pin "AK2") (pinfunction "1_AK2") (pintype "bidirectional"))
      (node (ref "U2") (pin "13") (pinfunction "O_13") (pintype "open_collector"))
    )
    (net (code "173") (name "~{MEM_START}") (class "Default")
      (node (ref "U$2") (pin "AJ2") (pinfunction "1_AJ2") (pintype "bidirectional"))
    )
    (net (code "174") (name "~{MS_DISABLE}") (class "Default")
      (node (ref "U$2") (pin "CV1") (pinfunction "1_CV1") (pintype "bidirectional"))
    )
    (net (code "175") (name "~{NOT_LAST_TR}") (class "Default")
      (node (ref "U$2") (pin "CM1") (pinfunction "1_CM1") (pintype "bidirectional"))
    )
    (net (code "176") (name "~{NTS_STALL}") (class "Default")
      (node (ref "U$2") (pin "BR2") (pinfunction "1_BR2") (pintype "bidirectional"))
    )
    (net (code "177") (name "~{OVERFLOW}") (class "Default")
      (node (ref "U$2") (pin "BJ2") (pinfunction "1_BJ2") (pintype "bidirectional"))
    )
    (net (code "178") (name "~{ROM_ADDR}") (class "Default")
      (node (ref "U$2") (pin "AU2") (pinfunction "1_AU2") (pintype "bidirectional"))
    )
    (net (code "179") (name "~{RUN}") (class "Default")
      (node (ref "U$2") (pin "BU2") (pinfunction "1_BU2") (pintype "bidirectional"))
    )
    (net (code "180") (name "~{SKIP}") (class "Default")
      (node (ref "U$2") (pin "CS1") (pinfunction "1_CS1") (pintype "bidirectional"))
    )
    (net (code "181") (name "~{STOP}") (class "Default")
      (node (ref "U$2") (pin "DS2") (pinfunction "1_DS2") (pintype "bidirectional"))
    )
    (net (code "182") (name "~{TS1}") (class "Default")
      (node (ref "U$2") (pin "CK2") (pinfunction "1_CK2") (pintype "bidirectional"))
    )
    (net (code "183") (name "~{TS2}") (class "Default")
      (node (ref "U$2") (pin "CL2") (pinfunction "1_CL2") (pintype "bidirectional"))
    )
    (net (code "184") (name "~{TS3}") (class "Default")
      (node (ref "U$2") (pin "CM2") (pinfunction "1_CM2") (pintype "bidirectional"))
    )
    (net (code "185") (name "~{TS4}") (class "Default")
      (node (ref "U$2") (pin "CP2") (pinfunction "1_CP2") (pintype "bidirectional"))
    )
    (net (code "186") (name "~{USER_MODE}") (class "Default")
      (node (ref "U$2") (pin "DM2") (pinfunction "1_DM2") (pintype "bidirectional"))
    )
  )
)
